# 5VBuch_RUDRV2.net
KiCad netlist of a schematic drawn in Altium Designer
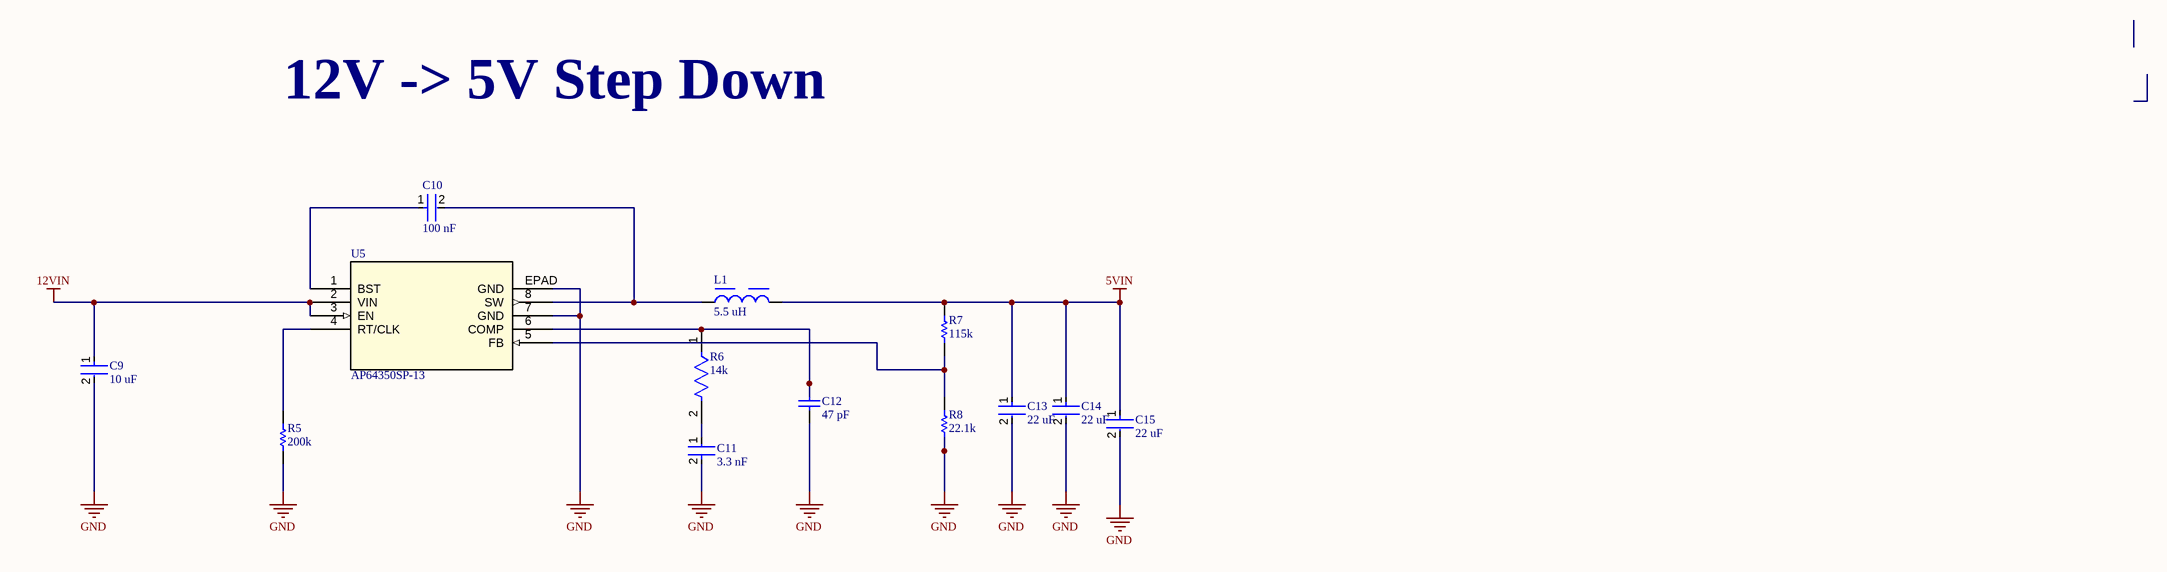
[diagram p0: 5VBuch_RUDRV2.SchDoc]

(export (version "E")
  (design (tool "Eeschema 10.0.6"))
  (components
    (comp (ref "C9")
      (value "10 uF")
      (footprint "FP-GRM21B-0_1-IPC_C")
      (description "Chip Multilayer Ceramic Capacitors for General Purpose, 0805, 10uF, X5R, 15%, 10%, 16V")
      (fields (field (name "TOLERANCE") "10%") (field (name "VOLTAGE") "16V"))
      (libsource (lib "Altium Content Vault") (part "b4654b650e69147ec39a6b967a45e02"))
    )
    (comp (ref "C10")
      (value "100 nF")
      (footprint "FP-0805-L_2_01_0_2-W_1_25-IPC_B")
      (description "Automotive Ceramic Capacitor, 0805, 100nF, 10%, X7R, 15%, 100V")
      (fields (field (name "TOLERANCE") "10%") (field (name "VOLTAGE") "100V"))
      (libsource (lib "Altium Content Vault") (part "b4654b650e69147ec39a6b967a45e02"))
    )
    (comp (ref "C11")
      (value "3.3 nF")
      (footprint "FP-GRM216-0_1-IPC_B")
      (description "Chip Multilayer Ceramic Capacitors for General Purpose, 0805, 3300pF, C0G, 30ppm/°C, 5%, 50V")
      (fields (field (name "VOLTAGE") "50V") (field (name "TOLERANCE") "5%"))
      (libsource (lib "Altium Content Vault") (part "236180d848d6139a670b325ea6854c9"))
    )
    (comp (ref "C12")
      (value "47 pF")
      (footprint "CAPC2013X135X50NL15T20")
      (fields (field (name "PART NUMBER") "VJ0805A470JXACW1BC") (field (name "MANUFACTURER") "Vitramon"))
      (libsource (lib "Altium Content Vault") (part "CAP"))
    )
    (comp (ref "C13")
      (value "22 uF")
      (footprint "FP-GRM21B-0_15-MFG")
      (description "Chip Multilayer Ceramic Capacitors for General Purpose, 0805, 22uF, X5R, 15%, 20%, 6.3V")
      (fields (field (name "VOLTAGE") "6.3V") (field (name "TOLERANCE") "20%"))
      (libsource (lib "Altium Content Vault") (part "b4654b650e69147ec39a6b967a45e02"))
    )
    (comp (ref "C14")
      (value "22 uF")
      (footprint "FP-GRM21B-0_15-MFG")
      (description "Chip Multilayer Ceramic Capacitors for General Purpose, 0805, 22uF, X5R, 15%, 20%, 6.3V")
      (fields (field (name "VOLTAGE") "6.3V") (field (name "TOLERANCE") "20%"))
      (libsource (lib "Altium Content Vault") (part "b4654b650e69147ec39a6b967a45e02"))
    )
    (comp (ref "C15")
      (value "22 uF")
      (footprint "FP-GRM21B-0_15-MFG")
      (description "Chip Multilayer Ceramic Capacitors for General Purpose, 0805, 22uF, X5R, 15%, 20%, 6.3V")
      (fields (field (name "VOLTAGE") "6.3V") (field (name "TOLERANCE") "20%"))
      (libsource (lib "Altium Content Vault") (part "b4654b650e69147ec39a6b967a45e02"))
    )
    (comp (ref "L1")
      (value "5.5 uH")
      (footprint "WE-HCI_1050")
      (fields (field (name "TOLERANCE") "20%"))
      (libsource (lib "Altium Content Vault") (part "Inductor - 3"))
    )
    (comp (ref "R5")
      (value "200k")
      (footprint "RESC2013X70X40ML20T20")
      (fields (field (name "PART NUMBER") "ERJ-6GEYJ204V") (field (name "MANUFACTURER") "Panasonic"))
      (libsource (lib "Altium Content Vault") (part "RES"))
    )
    (comp (ref "R6")
      (value "14k")
      (footprint "FP-CRCW0805-e3-MFG")
      (description "RES Thick Film, 14kΩ, 1%, 0.125W, 100ppm/°C, 0805")
      (fields (field (name "TOLERANCE") "1%"))
      (libsource (lib "Altium Content Vault") (part "1029c3af85768c4190bb7ad29bc67b5"))
    )
    (comp (ref "R7")
      (value "115k")
      (footprint "RESC2013X50X30LL20T20")
      (fields (field (name "MANUFACTURER") "Vishay Dale") (field (name "PART NUMBER") "CRCW0805115KFKEA"))
      (libsource (lib "Altium Content Vault") (part "RES"))
    )
    (comp (ref "R8")
      (value "22.1k")
      (footprint "RESC2013X70X40NL20T20")
      (fields (field (name "PART NUMBER") "ERJ-6ENF2212V") (field (name "MANUFACTURER") "Panasonic"))
      (libsource (lib "Altium Content Vault") (part "RES"))
    )
    (comp (ref "U5")
      (value "AP64350SP-13")
      (footprint "SO-8EP_DIO")
      (description "No Description Available")
      (libsource (lib "AP64350SP-13") (part "AP64350SP-13"))
    )
  )
  (nets
    (net (code "1") (name "5VIN") (class "Default")
      (node (ref "C13") (pin "1") (pinfunction "1_1") (pintype "passive"))
      (node (ref "C14") (pin "1") (pinfunction "1_1") (pintype "passive"))
      (node (ref "C15") (pin "1") (pinfunction "1_1") (pintype "passive"))
      (node (ref "L1") (pin "2") (pinfunction "2_2") (pintype "passive"))
      (node (ref "R7") (pin "2") (pinfunction "2_2") (pintype "passive"))
    )
    (net (code "2") (name "12VIN") (class "Default")
      (node (ref "C9") (pin "1") (pinfunction "1_1") (pintype "passive"))
      (node (ref "U5") (pin "2") (pinfunction "VIN_2") (pintype "power_in"))
      (node (ref "U5") (pin "3") (pinfunction "EN_3") (pintype "input"))
    )
    (net (code "3") (name "GND") (class "Default")
      (node (ref "C11") (pin "2") (pinfunction "2_2") (pintype "passive"))
      (node (ref "C12") (pin "1") (pinfunction "1_1") (pintype "passive"))
      (node (ref "C13") (pin "2") (pinfunction "2_2") (pintype "passive"))
      (node (ref "C14") (pin "2") (pinfunction "2_2") (pintype "passive"))
      (node (ref "C15") (pin "2") (pinfunction "2_2") (pintype "passive"))
      (node (ref "C9") (pin "2") (pinfunction "2_2") (pintype "passive"))
      (node (ref "R5") (pin "1") (pinfunction "1_1") (pintype "passive"))
      (node (ref "R8") (pin "1") (pinfunction "1_1") (pintype "passive"))
      (node (ref "U5") (pin "7") (pinfunction "GND_7") (pintype "power_in"))
      (node (ref "U5") (pin "EPAD") (pinfunction "GND_EPAD") (pintype "power_in"))
    )
    (net (code "4") (name "Net-(C11-Pad1)") (class "Default")
      (node (ref "C11") (pin "1") (pinfunction "1_1") (pintype "passive"))
      (node (ref "R6") (pin "2") (pinfunction "2_2") (pintype "passive"))
    )
    (net (code "5") (name "Net-(U5-BST)") (class "Default")
      (node (ref "C10") (pin "1") (pinfunction "1_1") (pintype "passive"))
      (node (ref "U5") (pin "1") (pinfunction "BST_1") (pintype "power_in"))
    )
    (net (code "6") (name "Net-(U5-COMP)") (class "Default")
      (node (ref "C12") (pin "2") (pinfunction "2_2") (pintype "passive"))
      (node (ref "R6") (pin "1") (pinfunction "1_1") (pintype "passive"))
      (node (ref "U5") (pin "6") (pinfunction "COMP_6") (pintype "passive"))
    )
    (net (code "7") (name "Net-(U5-FB)") (class "Default")
      (node (ref "R7") (pin "1") (pinfunction "1_1") (pintype "passive"))
      (node (ref "R8") (pin "2") (pinfunction "2_2") (pintype "passive"))
      (node (ref "U5") (pin "5") (pinfunction "FB_5") (pintype "input"))
    )
    (net (code "8") (name "Net-(U5-RT{slash}CLK)") (class "Default")
      (node (ref "R5") (pin "2") (pinfunction "2_2") (pintype "passive"))
      (node (ref "U5") (pin "4") (pinfunction "RT/CLK_4") (pintype "passive"))
    )
    (net (code "9") (name "Net-(U5-SW)") (class "Default")
      (node (ref "C10") (pin "2") (pinfunction "2_2") (pintype "passive"))
      (node (ref "L1") (pin "1") (pinfunction "1_1") (pintype "passive"))
      (node (ref "U5") (pin "8") (pinfunction "SW_8") (pintype "output"))
    )
  )
)
